# main.net
KiCad netlist of a schematic drawn in EAGLE
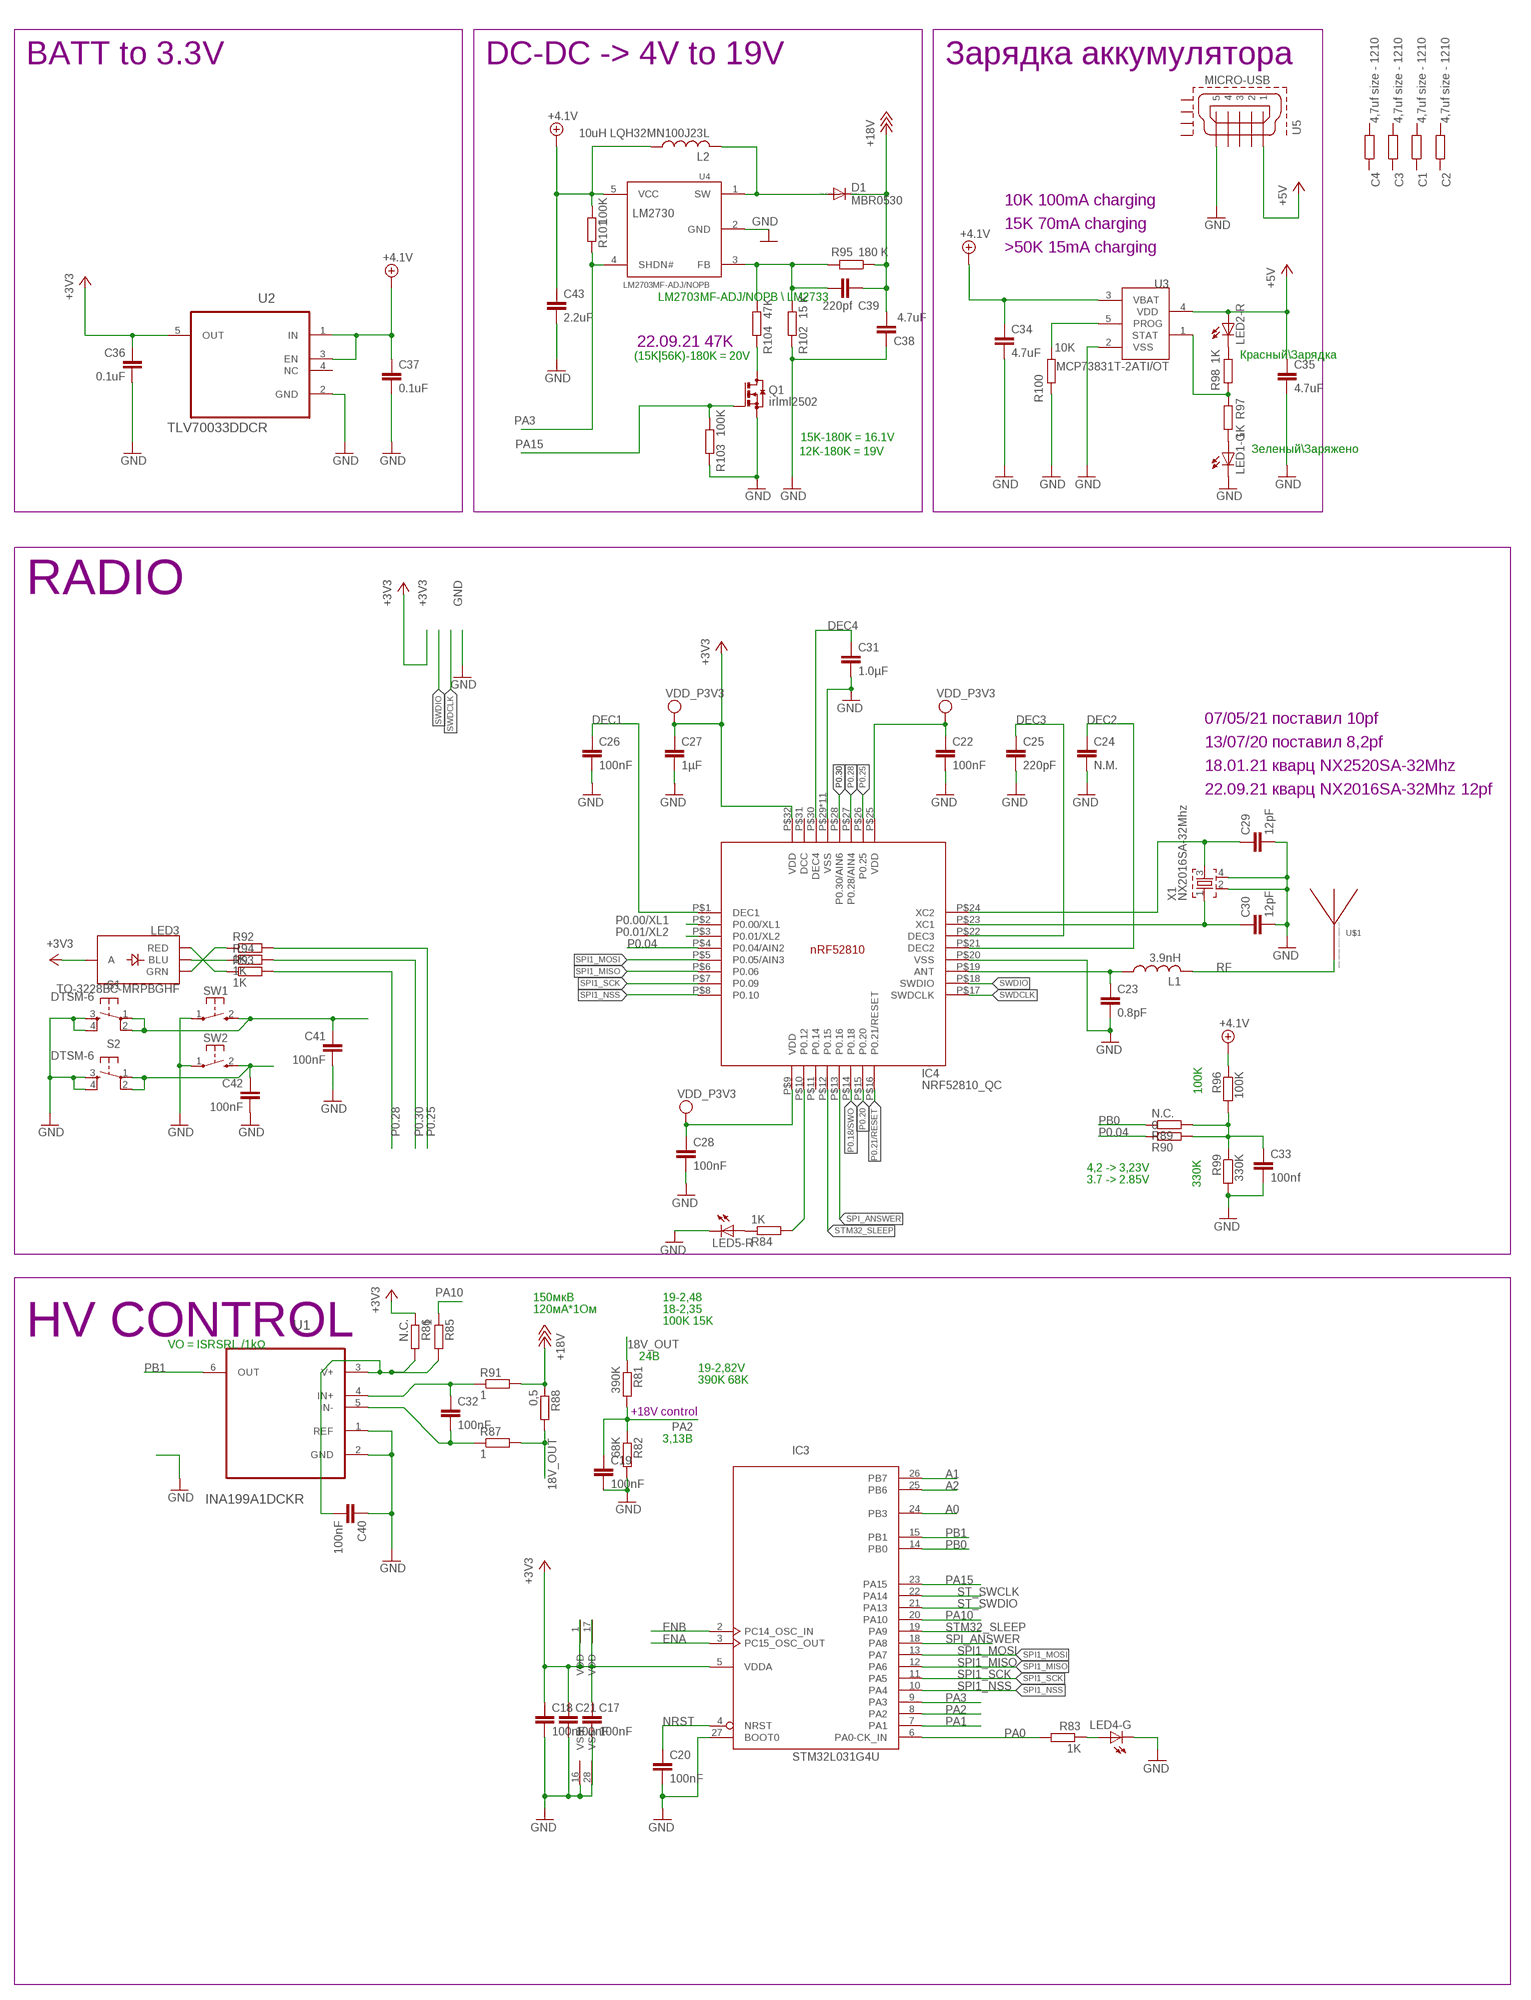
[diagram p0: schematic, sheet 1, part 1 of 2]
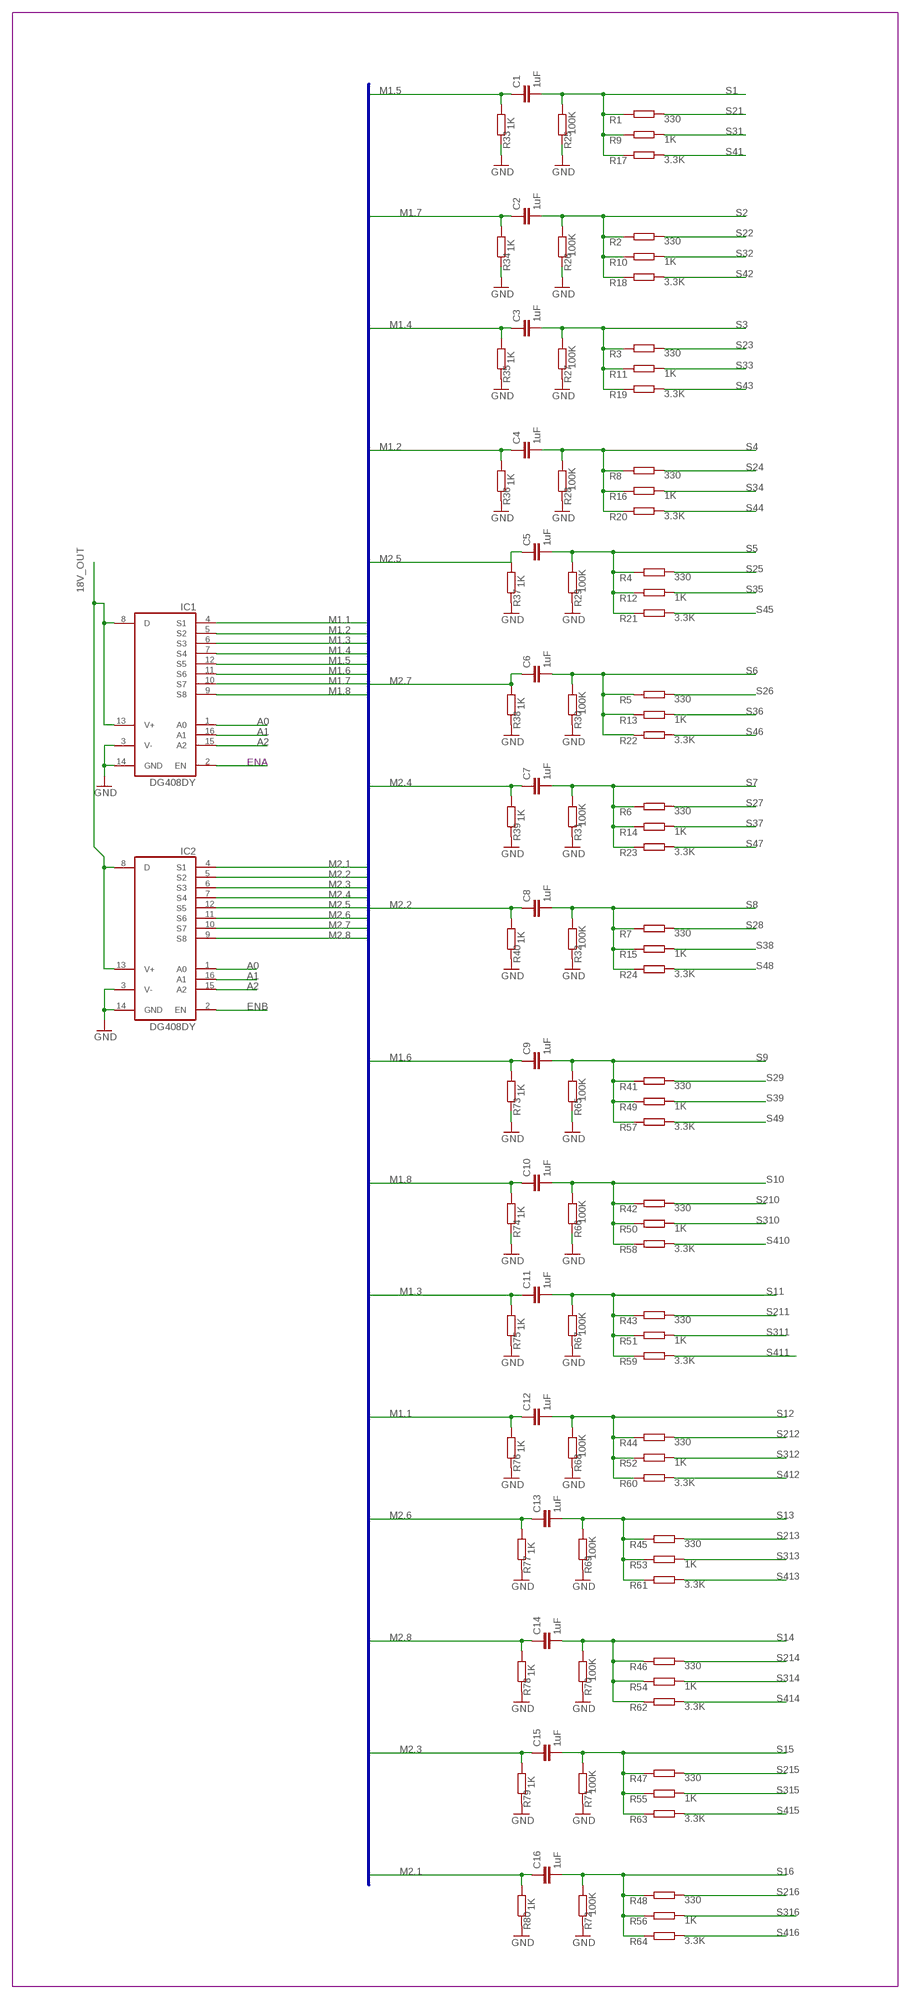
[diagram p1: schematic, sheet 1, part 2 of 2]

(export (version "E")
  (design (tool "Eeschema 10.0.6"))
  (components
    (comp (ref "C1")
      (value "1uF")
      (footprint "eagle-import:C0402")
      (libsource (lib "eagle-import") (part "C-EUC0402"))
    )
    (comp (ref "C2")
      (value "1uF")
      (footprint "eagle-import:C0402")
      (libsource (lib "eagle-import") (part "C-EUC0402"))
    )
    (comp (ref "C3")
      (value "1uF")
      (footprint "eagle-import:C0402")
      (libsource (lib "eagle-import") (part "C-EUC0402"))
    )
    (comp (ref "C4")
      (value "1uF")
      (footprint "eagle-import:C0402")
      (libsource (lib "eagle-import") (part "C-EUC0402"))
    )
    (comp (ref "C5")
      (value "1uF")
      (footprint "eagle-import:C0402")
      (libsource (lib "eagle-import") (part "C-EUC0402"))
    )
    (comp (ref "C6")
      (value "1uF")
      (footprint "eagle-import:C0402")
      (libsource (lib "eagle-import") (part "C-EUC0402"))
    )
    (comp (ref "C7")
      (value "1uF")
      (footprint "eagle-import:C0402")
      (libsource (lib "eagle-import") (part "C-EUC0402"))
    )
    (comp (ref "C8")
      (value "1uF")
      (footprint "eagle-import:C0402")
      (libsource (lib "eagle-import") (part "C-EUC0402"))
    )
    (comp (ref "C9")
      (value "1uF")
      (footprint "eagle-import:C0402")
      (libsource (lib "eagle-import") (part "C-EUC0402"))
    )
    (comp (ref "C10")
      (value "1uF")
      (footprint "eagle-import:C0402")
      (libsource (lib "eagle-import") (part "C-EUC0402"))
    )
    (comp (ref "C11")
      (value "1uF")
      (footprint "eagle-import:C0402")
      (libsource (lib "eagle-import") (part "C-EUC0402"))
    )
    (comp (ref "C12")
      (value "1uF")
      (footprint "eagle-import:C0402")
      (libsource (lib "eagle-import") (part "C-EUC0402"))
    )
    (comp (ref "C13")
      (value "1uF")
      (footprint "eagle-import:C0402")
      (libsource (lib "eagle-import") (part "C-EUC0402"))
    )
    (comp (ref "C14")
      (value "1uF")
      (footprint "eagle-import:C0402")
      (libsource (lib "eagle-import") (part "C-EUC0402"))
    )
    (comp (ref "C15")
      (value "1uF")
      (footprint "eagle-import:C0402")
      (libsource (lib "eagle-import") (part "C-EUC0402"))
    )
    (comp (ref "C16")
      (value "1uF")
      (footprint "eagle-import:C0402")
      (libsource (lib "eagle-import") (part "C-EUC0402"))
    )
    (comp (ref "C17")
      (value "100nF")
      (footprint "eagle-import:RESC0402_N")
      (libsource (lib "eagle-import") (part "CAPACITOR_0402_N"))
    )
    (comp (ref "C18")
      (value "100nF")
      (footprint "eagle-import:RESC0402_N")
      (libsource (lib "eagle-import") (part "CAPACITOR_0402_N"))
    )
    (comp (ref "C19")
      (value "100nF")
      (footprint "eagle-import:RESC0402_N")
      (libsource (lib "eagle-import") (part "CAPACITOR_0402_N"))
    )
    (comp (ref "C20")
      (value "100nF")
      (footprint "eagle-import:RESC0402_N")
      (libsource (lib "eagle-import") (part "CAPACITOR_0402_N"))
    )
    (comp (ref "C21")
      (value "100nF")
      (footprint "eagle-import:RESC0402_N")
      (libsource (lib "eagle-import") (part "CAPACITOR_0402_N"))
    )
    (comp (ref "C22")
      (value "100nF")
      (footprint "eagle-import:RESC0402_N")
      (libsource (lib "eagle-import") (part "CAPACITOR_0402_N"))
    )
    (comp (ref "C23")
      (value "0.8pF")
      (footprint "eagle-import:RESC0402_N")
      (libsource (lib "eagle-import") (part "CAPACITOR_0402_N"))
    )
    (comp (ref "C24")
      (value "N.M.")
      (footprint "eagle-import:RESC0402_N")
      (libsource (lib "eagle-import") (part "CAPACITOR_0402_N"))
    )
    (comp (ref "C25")
      (value "220pF")
      (footprint "eagle-import:RESC0402_N")
      (libsource (lib "eagle-import") (part "CAPACITOR_0402_N"))
    )
    (comp (ref "C26")
      (value "100nF")
      (footprint "eagle-import:RESC0402_N")
      (libsource (lib "eagle-import") (part "CAPACITOR_0402_N"))
    )
    (comp (ref "C27")
      (value "1µF")
      (footprint "eagle-import:RESC0603_N")
      (libsource (lib "eagle-import") (part "CAPACITOR_0603_N"))
    )
    (comp (ref "C28")
      (value "100nF")
      (footprint "eagle-import:RESC0402_N")
      (libsource (lib "eagle-import") (part "CAPACITOR_0402_N"))
    )
    (comp (ref "C29")
      (value "12pF")
      (footprint "eagle-import:RESC0402_N")
      (libsource (lib "eagle-import") (part "CAPACITOR_0402_N"))
    )
    (comp (ref "C30")
      (value "12pF")
      (footprint "eagle-import:RESC0402_N")
      (libsource (lib "eagle-import") (part "CAPACITOR_0402_N"))
    )
    (comp (ref "C31")
      (value "1.0µF")
      (footprint "eagle-import:RESC0402_M")
      (libsource (lib "eagle-import") (part "CAPACITOR_0402_M"))
    )
    (comp (ref "C32")
      (value "100nF")
      (footprint "eagle-import:RESC0402_N")
      (libsource (lib "eagle-import") (part "CAPACITOR_0402_N"))
    )
    (comp (ref "C33")
      (value "100nf")
      (footprint "eagle-import:RESC0402_N")
      (libsource (lib "eagle-import") (part "CAPACITOR_0402_N"))
    )
    (comp (ref "C34")
      (value "4.7uF")
      (footprint "eagle-import:C0805K")
      (libsource (lib "eagle-import") (part "C-EUC0805K"))
    )
    (comp (ref "C35")
      (value "4.7uF")
      (footprint "eagle-import:C0805K")
      (libsource (lib "eagle-import") (part "C-EUC0805K"))
    )
    (comp (ref "C36")
      (value "0.1uF")
      (footprint "eagle-import:C0402")
      (libsource (lib "eagle-import") (part "C-EUC0402"))
    )
    (comp (ref "C37")
      (value "0.1uF")
      (footprint "eagle-import:C0402")
      (libsource (lib "eagle-import") (part "C-EUC0402"))
    )
    (comp (ref "C38")
      (value "4.7uF")
      (footprint "eagle-import:C0805K")
      (libsource (lib "eagle-import") (part "C-EUC0805K"))
    )
    (comp (ref "C39")
      (value "220pf")
      (footprint "eagle-import:C0603K")
      (libsource (lib "eagle-import") (part "C-EUC0603K"))
    )
    (comp (ref "C40")
      (value "100nF")
      (footprint "eagle-import:RESC0402_N")
      (libsource (lib "eagle-import") (part "CAPACITOR_0402_N"))
    )
    (comp (ref "C41")
      (value "100nF")
      (footprint "eagle-import:RESC0402_N")
      (libsource (lib "eagle-import") (part "CAPACITOR_0402_N"))
    )
    (comp (ref "C42")
      (value "100nF")
      (footprint "eagle-import:RESC0402_N")
      (libsource (lib "eagle-import") (part "CAPACITOR_0402_N"))
    )
    (comp (ref "C43")
      (value "2.2uF")
      (footprint "eagle-import:C0805K")
      (libsource (lib "eagle-import") (part "C-EUC0805K"))
    )
    (comp (ref "D1")
      (value "MBR0530")
      (footprint "eagle-import:SOD123")
      (libsource (lib "eagle-import") (part "MBR0520LT"))
    )
    (comp (ref "IC1")
      (value "DG408DY")
      (footprint "eagle-import:SO16")
      (libsource (lib "eagle-import") (part "DG408DY"))
    )
    (comp (ref "IC2")
      (value "DG408DY")
      (footprint "eagle-import:SO16")
      (libsource (lib "eagle-import") (part "DG408DY"))
    )
    (comp (ref "IC3")
      (value "STM32L031G4U")
      (footprint "eagle-import:UFQFPN28")
      (libsource (lib "eagle-import") (part "STM32L031GU4"))
    )
    (comp (ref "IC4")
      (value "NRF52810_QC")
      (footprint "eagle-import:QFN50P500X500X90-32_N")
      (libsource (lib "eagle-import") (part "NRF52810_QC"))
    )
    (comp (ref "L1")
      (value "3.9nH")
      (footprint "eagle-import:RESC0402_N")
      (libsource (lib "eagle-import") (part "INDUCTOR_0402_N"))
    )
    (comp (ref "L2")
      (value "10uH LQH32MN100J23L")
      (footprint "eagle-import:L2825P")
      (libsource (lib "eagle-import") (part "L-USL2825P"))
    )
    (comp (ref "LED1-G")
      (value "LEDCHIP-LED0603")
      (footprint "eagle-import:CHIP-LED0603")
      (libsource (lib "eagle-import") (part "LEDCHIP-LED0603"))
    )
    (comp (ref "LED2-R")
      (value "LEDCHIP-LED0603")
      (footprint "eagle-import:CHIP-LED0603")
      (libsource (lib "eagle-import") (part "LEDCHIP-LED0603"))
    )
    (comp (ref "LED3")
      (value "TO-3228BC-MRPBGHF")
      (footprint "eagle-import:LED-TRICOLOR-SMD")
      (libsource (lib "eagle-import") (part "LED-RGB-CASMD"))
    )
    (comp (ref "LED4-G")
      (value "LEDCHIPLED_0603")
      (footprint "eagle-import:CHIPLED_0603")
      (libsource (lib "eagle-import") (part "LEDCHIPLED_0603"))
    )
    (comp (ref "LED5-R")
      (value "LEDCHIPLED_0603")
      (footprint "eagle-import:CHIPLED_0603")
      (libsource (lib "eagle-import") (part "LEDCHIPLED_0603"))
    )
    (comp (ref "Q1")
      (value "irlml2502")
      (footprint "eagle-import:SOT23")
      (libsource (lib "eagle-import") (part "IRLML_N_TYPE"))
    )
    (comp (ref "R1")
      (value "330")
      (footprint "eagle-import:R0402")
      (libsource (lib "eagle-import") (part "R-EU_R0402"))
    )
    (comp (ref "R2")
      (value "330")
      (footprint "eagle-import:R0402")
      (libsource (lib "eagle-import") (part "R-EU_R0402"))
    )
    (comp (ref "R3")
      (value "330")
      (footprint "eagle-import:R0402")
      (libsource (lib "eagle-import") (part "R-EU_R0402"))
    )
    (comp (ref "R4")
      (value "330")
      (footprint "eagle-import:R0402")
      (libsource (lib "eagle-import") (part "R-EU_R0402"))
    )
    (comp (ref "R5")
      (value "330")
      (footprint "eagle-import:R0402")
      (libsource (lib "eagle-import") (part "R-EU_R0402"))
    )
    (comp (ref "R6")
      (value "330")
      (footprint "eagle-import:R0402")
      (libsource (lib "eagle-import") (part "R-EU_R0402"))
    )
    (comp (ref "R7")
      (value "330")
      (footprint "eagle-import:R0402")
      (libsource (lib "eagle-import") (part "R-EU_R0402"))
    )
    (comp (ref "R8")
      (value "330")
      (footprint "eagle-import:R0402")
      (libsource (lib "eagle-import") (part "R-EU_R0402"))
    )
    (comp (ref "R9")
      (value "1K")
      (footprint "eagle-import:R0402")
      (libsource (lib "eagle-import") (part "R-EU_R0402"))
    )
    (comp (ref "R10")
      (value "1K")
      (footprint "eagle-import:R0402")
      (libsource (lib "eagle-import") (part "R-EU_R0402"))
    )
    (comp (ref "R11")
      (value "1K")
      (footprint "eagle-import:R0402")
      (libsource (lib "eagle-import") (part "R-EU_R0402"))
    )
    (comp (ref "R12")
      (value "1K")
      (footprint "eagle-import:R0402")
      (libsource (lib "eagle-import") (part "R-EU_R0402"))
    )
    (comp (ref "R13")
      (value "1K")
      (footprint "eagle-import:R0402")
      (libsource (lib "eagle-import") (part "R-EU_R0402"))
    )
    (comp (ref "R14")
      (value "1K")
      (footprint "eagle-import:R0402")
      (libsource (lib "eagle-import") (part "R-EU_R0402"))
    )
    (comp (ref "R15")
      (value "1K")
      (footprint "eagle-import:R0402")
      (libsource (lib "eagle-import") (part "R-EU_R0402"))
    )
    (comp (ref "R16")
      (value "1K")
      (footprint "eagle-import:R0402")
      (libsource (lib "eagle-import") (part "R-EU_R0402"))
    )
    (comp (ref "R17")
      (value "3.3K")
      (footprint "eagle-import:R0402")
      (libsource (lib "eagle-import") (part "R-EU_R0402"))
    )
    (comp (ref "R18")
      (value "3.3K")
      (footprint "eagle-import:R0402")
      (libsource (lib "eagle-import") (part "R-EU_R0402"))
    )
    (comp (ref "R19")
      (value "3.3K")
      (footprint "eagle-import:R0402")
      (libsource (lib "eagle-import") (part "R-EU_R0402"))
    )
    (comp (ref "R20")
      (value "3.3K")
      (footprint "eagle-import:R0402")
      (libsource (lib "eagle-import") (part "R-EU_R0402"))
    )
    (comp (ref "R21")
      (value "3.3K")
      (footprint "eagle-import:R0402")
      (libsource (lib "eagle-import") (part "R-EU_R0402"))
    )
    (comp (ref "R22")
      (value "3.3K")
      (footprint "eagle-import:R0402")
      (libsource (lib "eagle-import") (part "R-EU_R0402"))
    )
    (comp (ref "R23")
      (value "3.3K")
      (footprint "eagle-import:R0402")
      (libsource (lib "eagle-import") (part "R-EU_R0402"))
    )
    (comp (ref "R24")
      (value "3.3K")
      (footprint "eagle-import:R0402")
      (libsource (lib "eagle-import") (part "R-EU_R0402"))
    )
    (comp (ref "R25")
      (value "100K")
      (footprint "eagle-import:R0402")
      (libsource (lib "eagle-import") (part "R-EU_R0402"))
    )
    (comp (ref "R26")
      (value "100K")
      (footprint "eagle-import:R0402")
      (libsource (lib "eagle-import") (part "R-EU_R0402"))
    )
    (comp (ref "R27")
      (value "100K")
      (footprint "eagle-import:R0402")
      (libsource (lib "eagle-import") (part "R-EU_R0402"))
    )
    (comp (ref "R28")
      (value "100K")
      (footprint "eagle-import:R0402")
      (libsource (lib "eagle-import") (part "R-EU_R0402"))
    )
    (comp (ref "R29")
      (value "100K")
      (footprint "eagle-import:R0402")
      (libsource (lib "eagle-import") (part "R-EU_R0402"))
    )
    (comp (ref "R30")
      (value "100K")
      (footprint "eagle-import:R0402")
      (libsource (lib "eagle-import") (part "R-EU_R0402"))
    )
    (comp (ref "R31")
      (value "100K")
      (footprint "eagle-import:R0402")
      (libsource (lib "eagle-import") (part "R-EU_R0402"))
    )
    (comp (ref "R32")
      (value "100K")
      (footprint "eagle-import:R0402")
      (libsource (lib "eagle-import") (part "R-EU_R0402"))
    )
    (comp (ref "R33")
      (value "1K")
      (footprint "eagle-import:R0402")
      (libsource (lib "eagle-import") (part "R-EU_R0402"))
    )
    (comp (ref "R34")
      (value "1K")
      (footprint "eagle-import:R0402")
      (libsource (lib "eagle-import") (part "R-EU_R0402"))
    )
    (comp (ref "R35")
      (value "1K")
      (footprint "eagle-import:R0402")
      (libsource (lib "eagle-import") (part "R-EU_R0402"))
    )
    (comp (ref "R36")
      (value "1K")
      (footprint "eagle-import:R0402")
      (libsource (lib "eagle-import") (part "R-EU_R0402"))
    )
    (comp (ref "R37")
      (value "1K")
      (footprint "eagle-import:R0402")
      (libsource (lib "eagle-import") (part "R-EU_R0402"))
    )
    (comp (ref "R38")
      (value "1K")
      (footprint "eagle-import:R0402")
      (libsource (lib "eagle-import") (part "R-EU_R0402"))
    )
    (comp (ref "R39")
      (value "1K")
      (footprint "eagle-import:R0402")
      (libsource (lib "eagle-import") (part "R-EU_R0402"))
    )
    (comp (ref "R40")
      (value "1K")
      (footprint "eagle-import:R0402")
      (libsource (lib "eagle-import") (part "R-EU_R0402"))
    )
    (comp (ref "R41")
      (value "330")
      (footprint "eagle-import:R0402")
      (libsource (lib "eagle-import") (part "R-EU_R0402"))
    )
    (comp (ref "R42")
      (value "330")
      (footprint "eagle-import:R0402")
      (libsource (lib "eagle-import") (part "R-EU_R0402"))
    )
    (comp (ref "R43")
      (value "330")
      (footprint "eagle-import:R0402")
      (libsource (lib "eagle-import") (part "R-EU_R0402"))
    )
    (comp (ref "R44")
      (value "330")
      (footprint "eagle-import:R0402")
      (libsource (lib "eagle-import") (part "R-EU_R0402"))
    )
    (comp (ref "R45")
      (value "330")
      (footprint "eagle-import:R0402")
      (libsource (lib "eagle-import") (part "R-EU_R0402"))
    )
    (comp (ref "R46")
      (value "330")
      (footprint "eagle-import:R0402")
      (libsource (lib "eagle-import") (part "R-EU_R0402"))
    )
    (comp (ref "R47")
      (value "330")
      (footprint "eagle-import:R0402")
      (libsource (lib "eagle-import") (part "R-EU_R0402"))
    )
    (comp (ref "R48")
      (value "330")
      (footprint "eagle-import:R0402")
      (libsource (lib "eagle-import") (part "R-EU_R0402"))
    )
    (comp (ref "R49")
      (value "1K")
      (footprint "eagle-import:R0402")
      (libsource (lib "eagle-import") (part "R-EU_R0402"))
    )
    (comp (ref "R50")
      (value "1K")
      (footprint "eagle-import:R0402")
      (libsource (lib "eagle-import") (part "R-EU_R0402"))
    )
    (comp (ref "R51")
      (value "1K")
      (footprint "eagle-import:R0402")
      (libsource (lib "eagle-import") (part "R-EU_R0402"))
    )
    (comp (ref "R52")
      (value "1K")
      (footprint "eagle-import:R0402")
      (libsource (lib "eagle-import") (part "R-EU_R0402"))
    )
    (comp (ref "R53")
      (value "1K")
      (footprint "eagle-import:R0402")
      (libsource (lib "eagle-import") (part "R-EU_R0402"))
    )
    (comp (ref "R54")
      (value "1K")
      (footprint "eagle-import:R0402")
      (libsource (lib "eagle-import") (part "R-EU_R0402"))
    )
    (comp (ref "R55")
      (value "1K")
      (footprint "eagle-import:R0402")
      (libsource (lib "eagle-import") (part "R-EU_R0402"))
    )
    (comp (ref "R56")
      (value "1K")
      (footprint "eagle-import:R0402")
      (libsource (lib "eagle-import") (part "R-EU_R0402"))
    )
    (comp (ref "R57")
      (value "3.3K")
      (footprint "eagle-import:R0402")
      (libsource (lib "eagle-import") (part "R-EU_R0402"))
    )
    (comp (ref "R58")
      (value "3.3K")
      (footprint "eagle-import:R0402")
      (libsource (lib "eagle-import") (part "R-EU_R0402"))
    )
    (comp (ref "R59")
      (value "3.3K")
      (footprint "eagle-import:R0402")
      (libsource (lib "eagle-import") (part "R-EU_R0402"))
    )
    (comp (ref "R60")
      (value "3.3K")
      (footprint "eagle-import:R0402")
      (libsource (lib "eagle-import") (part "R-EU_R0402"))
    )
    (comp (ref "R61")
      (value "3.3K")
      (footprint "eagle-import:R0402")
      (libsource (lib "eagle-import") (part "R-EU_R0402"))
    )
    (comp (ref "R62")
      (value "3.3K")
      (footprint "eagle-import:R0402")
      (libsource (lib "eagle-import") (part "R-EU_R0402"))
    )
    (comp (ref "R63")
      (value "3.3K")
      (footprint "eagle-import:R0402")
      (libsource (lib "eagle-import") (part "R-EU_R0402"))
    )
    (comp (ref "R64")
      (value "3.3K")
      (footprint "eagle-import:R0402")
      (libsource (lib "eagle-import") (part "R-EU_R0402"))
    )
    (comp (ref "R65")
      (value "100K")
      (footprint "eagle-import:R0402")
      (libsource (lib "eagle-import") (part "R-EU_R0402"))
    )
    (comp (ref "R66")
      (value "100K")
      (footprint "eagle-import:R0402")
      (libsource (lib "eagle-import") (part "R-EU_R0402"))
    )
    (comp (ref "R67")
      (value "100K")
      (footprint "eagle-import:R0402")
      (libsource (lib "eagle-import") (part "R-EU_R0402"))
    )
    (comp (ref "R68")
      (value "100K")
      (footprint "eagle-import:R0402")
      (libsource (lib "eagle-import") (part "R-EU_R0402"))
    )
    (comp (ref "R69")
      (value "100K")
      (footprint "eagle-import:R0402")
      (libsource (lib "eagle-import") (part "R-EU_R0402"))
    )
    (comp (ref "R70")
      (value "100K")
      (footprint "eagle-import:R0402")
      (libsource (lib "eagle-import") (part "R-EU_R0402"))
    )
    (comp (ref "R71")
      (value "100K")
      (footprint "eagle-import:R0402")
      (libsource (lib "eagle-import") (part "R-EU_R0402"))
    )
    (comp (ref "R72")
      (value "100K")
      (footprint "eagle-import:R0402")
      (libsource (lib "eagle-import") (part "R-EU_R0402"))
    )
    (comp (ref "R73")
      (value "1K")
      (footprint "eagle-import:R0402")
      (libsource (lib "eagle-import") (part "R-EU_R0402"))
    )
    (comp (ref "R74")
      (value "1K")
      (footprint "eagle-import:R0402")
      (libsource (lib "eagle-import") (part "R-EU_R0402"))
    )
    (comp (ref "R75")
      (value "1K")
      (footprint "eagle-import:R0402")
      (libsource (lib "eagle-import") (part "R-EU_R0402"))
    )
    (comp (ref "R76")
      (value "1K")
      (footprint "eagle-import:R0402")
      (libsource (lib "eagle-import") (part "R-EU_R0402"))
    )
    (comp (ref "R77")
      (value "1K")
      (footprint "eagle-import:R0402")
      (libsource (lib "eagle-import") (part "R-EU_R0402"))
    )
    (comp (ref "R78")
      (value "1K")
      (footprint "eagle-import:R0402")
      (libsource (lib "eagle-import") (part "R-EU_R0402"))
    )
    (comp (ref "R79")
      (value "1K")
      (footprint "eagle-import:R0402")
      (libsource (lib "eagle-import") (part "R-EU_R0402"))
    )
    (comp (ref "R80")
      (value "1K")
      (footprint "eagle-import:R0402")
      (libsource (lib "eagle-import") (part "R-EU_R0402"))
    )
    (comp (ref "R81")
      (value "390K")
      (footprint "eagle-import:R0402")
      (libsource (lib "eagle-import") (part "R-EU_R0402"))
    )
    (comp (ref "R82")
      (value "68K")
      (footprint "eagle-import:R0402")
      (libsource (lib "eagle-import") (part "R-EU_R0402"))
    )
    (comp (ref "R83")
      (value "1K")
      (footprint "eagle-import:R0603")
      (libsource (lib "eagle-import") (part "R-EU_R0603"))
    )
    (comp (ref "R84")
      (value "1K")
      (footprint "eagle-import:R0603")
      (libsource (lib "eagle-import") (part "R-EU_R0603"))
    )
    (comp (ref "R85")
      (value "1")
      (footprint "eagle-import:R0402")
      (libsource (lib "eagle-import") (part "R-EU_R0402"))
    )
    (comp (ref "R86")
      (value "N.C.")
      (footprint "eagle-import:R0402")
      (libsource (lib "eagle-import") (part "R-EU_R0402"))
    )
    (comp (ref "R87")
      (value "1")
      (footprint "eagle-import:R0402")
      (libsource (lib "eagle-import") (part "R-EU_R0402"))
    )
    (comp (ref "R88")
      (value "0,5")
      (footprint "eagle-import:R0603")
      (libsource (lib "eagle-import") (part "R-EU_R0603"))
    )
    (comp (ref "R89")
      (value "N.C.")
      (footprint "eagle-import:R0402")
      (libsource (lib "eagle-import") (part "R-EU_R0402"))
    )
    (comp (ref "R90")
      (value "0")
      (footprint "eagle-import:R0402")
      (libsource (lib "eagle-import") (part "R-EU_R0402"))
    )
    (comp (ref "R91")
      (value "1")
      (footprint "eagle-import:R0402")
      (libsource (lib "eagle-import") (part "R-EU_R0402"))
    )
    (comp (ref "R92")
      (value "1K")
      (footprint "eagle-import:R0402")
      (libsource (lib "eagle-import") (part "R-EU_R0402"))
    )
    (comp (ref "R93")
      (value "1K")
      (footprint "eagle-import:R0402")
      (libsource (lib "eagle-import") (part "R-EU_R0402"))
    )
    (comp (ref "R94")
      (value "1K")
      (footprint "eagle-import:R0402")
      (libsource (lib "eagle-import") (part "R-EU_R0402"))
    )
    (comp (ref "R95")
      (value "180 K")
      (footprint "eagle-import:R0603")
      (libsource (lib "eagle-import") (part "R-EU_R0603"))
    )
    (comp (ref "R96")
      (value "100K")
      (footprint "eagle-import:R0402")
      (libsource (lib "eagle-import") (part "R-EU_R0402"))
    )
    (comp (ref "R97")
      (value "1K")
      (footprint "eagle-import:R0603")
      (libsource (lib "eagle-import") (part "R-EU_R0603"))
    )
    (comp (ref "R98")
      (value "1K")
      (footprint "eagle-import:R0603")
      (libsource (lib "eagle-import") (part "R-EU_R0603"))
    )
    (comp (ref "R99")
      (value "330K")
      (footprint "eagle-import:R0402")
      (libsource (lib "eagle-import") (part "R-EU_R0402"))
    )
    (comp (ref "R100")
      (value "10K")
      (footprint "eagle-import:R0402")
      (libsource (lib "eagle-import") (part "R-EU_R0402"))
    )
    (comp (ref "R101")
      (value "100K")
      (footprint "eagle-import:R0402")
      (libsource (lib "eagle-import") (part "R-EU_R0402"))
    )
    (comp (ref "R102")
      (value "15 K")
      (footprint "eagle-import:R0603")
      (libsource (lib "eagle-import") (part "R-EU_R0603"))
    )
    (comp (ref "R103")
      (value "100K")
      (footprint "eagle-import:R0603")
      (libsource (lib "eagle-import") (part "R-EU_R0603"))
    )
    (comp (ref "R104")
      (value "47K")
      (footprint "eagle-import:R0603")
      (libsource (lib "eagle-import") (part "R-EU_R0603"))
    )
    (comp (ref "S1")
      (value "DTSM-6")
      (footprint "eagle-import:DTSM-6")
      (libsource (lib "eagle-import") (part "DTSM-6"))
    )
    (comp (ref "S2")
      (value "DTSM-6")
      (footprint "eagle-import:DTSM-6")
      (libsource (lib "eagle-import") (part "DTSM-6"))
    )
    (comp (ref "SW1")
      (value "KSS-2EG4430")
      (footprint "eagle-import:KSS-2EG4430")
      (libsource (lib "eagle-import") (part "KSS-2EG4430"))
    )
    (comp (ref "SW2")
      (value "KSS-2EG4430")
      (footprint "eagle-import:KSS-2EG4430")
      (libsource (lib "eagle-import") (part "KSS-2EG4430"))
    )
    (comp (ref "U$1")
      (value "ANTENNA_QUARTER-WAVE_MONOPOLE_MEANDERED_LEFT")
      (footprint "eagle-import:QWMP_MEANDERED_LEFT_+6")
      (libsource (lib "eagle-import") (part "ANTENNA_QUARTER-WAVE_MONOPOLE_MEANDERED_LEFT"))
    )
    (comp (ref "U1")
      (value "INA199A1DCKR")
      (footprint "eagle-import:SOT65P210X110-6N")
      (libsource (lib "eagle-import") (part "INA199A1DCKR"))
    )
    (comp (ref "U2")
      (value "TLV70033DDCR")
      (footprint "eagle-import:SOT95P280X110-5N")
      (libsource (lib "eagle-import") (part "TLV70033DDCR"))
    )
    (comp (ref "U3")
      (value "MCP73831T-2ATI/OT")
      (footprint "eagle-import:SOT23-5L")
      (libsource (lib "eagle-import") (part "MCP73831"))
    )
    (comp (ref "U4")
      (value "LM2703MF-ADJ/NOPB")
      (footprint "eagle-import:SOT23-5")
      (libsource (lib "eagle-import") (part "LM2703"))
    )
    (comp (ref "U5")
      (value "MICRO-USB")
      (footprint "eagle-import:47589-0001")
      (libsource (lib "eagle-import") (part "MICRO-USB-RECEPTACLE47589-0001"))
    )
    (comp (ref "X1")
      (value "NX2016SA-32Mhz")
      (footprint "eagle-import:BT-XTAL_2016_N")
      (libsource (lib "eagle-import") (part "XTAL_32MHZ"))
    )
    (comp (ref "С1")
      (value "4,7uf size - 1210")
      (footprint "eagle-import:R1206")
      (libsource (lib "eagle-import") (part "R-EU_R1206"))
    )
    (comp (ref "С2")
      (value "4,7uf size - 1210")
      (footprint "eagle-import:R1206")
      (libsource (lib "eagle-import") (part "R-EU_R1206"))
    )
    (comp (ref "С3")
      (value "4,7uf size - 1210")
      (footprint "eagle-import:R1206")
      (libsource (lib "eagle-import") (part "R-EU_R1206"))
    )
    (comp (ref "С4")
      (value "4,7uf size - 1210")
      (footprint "eagle-import:R1206")
      (libsource (lib "eagle-import") (part "R-EU_R1206"))
    )
  )
  (nets
    (net (code "1") (name "+3V3") (class "Default")
      (node (ref "C17") (pin "1") (pinfunction "1_1") (pintype "passive"))
      (node (ref "C18") (pin "1") (pinfunction "1_1") (pintype "passive"))
      (node (ref "C21") (pin "1") (pinfunction "1_1") (pintype "passive"))
      (node (ref "C22") (pin "1") (pinfunction "1_1") (pintype "passive"))
      (node (ref "C27") (pin "1") (pinfunction "1_1") (pintype "passive"))
      (node (ref "C28") (pin "1") (pinfunction "1_1") (pintype "passive"))
      (node (ref "C36") (pin "1") (pinfunction "1_1") (pintype "passive"))
      (node (ref "IC3") (pin "1") (pinfunction "VDD_1") (pintype "power_in"))
      (node (ref "IC3") (pin "17") (pinfunction "VDD_17") (pintype "power_in"))
      (node (ref "IC3") (pin "5") (pinfunction "VDDA_5") (pintype "power_in"))
      (node (ref "IC4") (pin "P$25") (pinfunction "VDD_P$25") (pintype "bidirectional"))
      (node (ref "IC4") (pin "P$32") (pinfunction "VDD_P$32") (pintype "bidirectional"))
      (node (ref "IC4") (pin "P$9") (pinfunction "VDD_P$9") (pintype "bidirectional"))
      (node (ref "LED3") (pin "A") (pinfunction "A_A") (pintype "bidirectional"))
      (node (ref "R86") (pin "1") (pinfunction "1_1") (pintype "passive"))
      (node (ref "U2") (pin "5") (pinfunction "OUT_5") (pintype "output"))
    )
    (net (code "2") (name "+4.1V") (class "Default")
      (node (ref "C34") (pin "1") (pinfunction "1_1") (pintype "passive"))
      (node (ref "C37") (pin "1") (pinfunction "1_1") (pintype "passive"))
      (node (ref "C43") (pin "1") (pinfunction "1_1") (pintype "passive"))
      (node (ref "L2") (pin "1") (pinfunction "1_1") (pintype "passive"))
      (node (ref "R101") (pin "1") (pinfunction "1_1") (pintype "passive"))
      (node (ref "R96") (pin "1") (pinfunction "1_1") (pintype "passive"))
      (node (ref "U2") (pin "1") (pinfunction "IN_1") (pintype "power_in"))
      (node (ref "U2") (pin "3") (pinfunction "EN_3") (pintype "input"))
      (node (ref "U3") (pin "3") (pinfunction "VBAT_3") (pintype "bidirectional"))
      (node (ref "U4") (pin "5") (pinfunction "VCC_5") (pintype "power_in"))
    )
    (net (code "3") (name "+5V") (class "Default")
      (node (ref "C35") (pin "1") (pinfunction "1_1") (pintype "passive"))
      (node (ref "LED2-R") (pin "A") (pinfunction "A_A") (pintype "passive"))
      (node (ref "U3") (pin "4") (pinfunction "VDD_4") (pintype "bidirectional"))
      (node (ref "U5") (pin "1") (pinfunction "1_1") (pintype "input"))
    )
    (net (code "4") (name "+18V") (class "Default")
      (node (ref "C38") (pin "2") (pinfunction "2_2") (pintype "passive"))
      (node (ref "C39") (pin "1") (pinfunction "1_1") (pintype "passive"))
      (node (ref "D1") (pin "C") (pinfunction "C_C") (pintype "passive"))
      (node (ref "R88") (pin "1") (pinfunction "1_1") (pintype "passive"))
      (node (ref "R91") (pin "2") (pinfunction "2_2") (pintype "passive"))
      (node (ref "R95") (pin "1") (pinfunction "1_1") (pintype "passive"))
    )
    (net (code "5") (name "/18V_OUT") (class "Default")
      (node (ref "IC1") (pin "13") (pinfunction "V+_13") (pintype "power_in"))
      (node (ref "IC1") (pin "8") (pinfunction "D_8") (pintype "passive"))
      (node (ref "IC2") (pin "13") (pinfunction "V+_13") (pintype "power_in"))
      (node (ref "IC2") (pin "8") (pinfunction "D_8") (pintype "passive"))
      (node (ref "R81") (pin "1") (pinfunction "1_1") (pintype "passive"))
      (node (ref "R87") (pin "2") (pinfunction "2_2") (pintype "passive"))
      (node (ref "R88") (pin "2") (pinfunction "2_2") (pintype "passive"))
    )
    (net (code "6") (name "/A0") (class "Default")
      (node (ref "IC1") (pin "1") (pinfunction "A0_1") (pintype "input"))
      (node (ref "IC2") (pin "1") (pinfunction "A0_1") (pintype "input"))
      (node (ref "IC3") (pin "24") (pinfunction "PB3_24") (pintype "bidirectional"))
    )
    (net (code "7") (name "/A1") (class "Default")
      (node (ref "IC1") (pin "16") (pinfunction "A1_16") (pintype "input"))
      (node (ref "IC2") (pin "16") (pinfunction "A1_16") (pintype "input"))
      (node (ref "IC3") (pin "26") (pinfunction "PB7_26") (pintype "bidirectional"))
    )
    (net (code "8") (name "/A2") (class "Default")
      (node (ref "IC1") (pin "15") (pinfunction "A2_15") (pintype "input"))
      (node (ref "IC2") (pin "15") (pinfunction "A2_15") (pintype "input"))
      (node (ref "IC3") (pin "25") (pinfunction "PB6_25") (pintype "bidirectional"))
    )
    (net (code "9") (name "/DEC1") (class "Default")
      (node (ref "C26") (pin "1") (pinfunction "1_1") (pintype "passive"))
      (node (ref "IC4") (pin "P$1") (pinfunction "DEC1_P$1") (pintype "bidirectional"))
    )
    (net (code "10") (name "/DEC2") (class "Default")
      (node (ref "C24") (pin "1") (pinfunction "1_1") (pintype "passive"))
      (node (ref "IC4") (pin "P$21") (pinfunction "DEC2_P$21") (pintype "bidirectional"))
    )
    (net (code "11") (name "/DEC3") (class "Default")
      (node (ref "C25") (pin "1") (pinfunction "1_1") (pintype "passive"))
      (node (ref "IC4") (pin "P$22") (pinfunction "DEC3_P$22") (pintype "bidirectional"))
    )
    (net (code "12") (name "/DEC4") (class "Default")
      (node (ref "C31") (pin "1") (pinfunction "1_1") (pintype "passive"))
      (node (ref "IC4") (pin "P$30") (pinfunction "DEC4_P$30") (pintype "bidirectional"))
    )
    (net (code "13") (name "/ENA") (class "Default")
      (node (ref "IC1") (pin "2") (pinfunction "EN_2") (pintype "input"))
      (node (ref "IC3") (pin "3") (pinfunction "PC15_OSC_OUT_3") (pintype "bidirectional"))
    )
    (net (code "14") (name "/ENB") (class "Default")
      (node (ref "IC2") (pin "2") (pinfunction "EN_2") (pintype "input"))
      (node (ref "IC3") (pin "2") (pinfunction "PC14_OSC_IN_2") (pintype "bidirectional"))
    )
    (net (code "15") (name "/M1.1") (class "Default")
      (node (ref "C12") (pin "1") (pinfunction "1_1") (pintype "passive"))
      (node (ref "IC1") (pin "4") (pinfunction "S1_4") (pintype "passive"))
      (node (ref "R76") (pin "2") (pinfunction "2_2") (pintype "passive"))
    )
    (net (code "16") (name "/M1.2") (class "Default")
      (node (ref "C4") (pin "1") (pinfunction "1_1") (pintype "passive"))
      (node (ref "IC1") (pin "5") (pinfunction "S2_5") (pintype "passive"))
      (node (ref "R36") (pin "2") (pinfunction "2_2") (pintype "passive"))
    )
    (net (code "17") (name "/M1.3") (class "Default")
      (node (ref "C11") (pin "1") (pinfunction "1_1") (pintype "passive"))
      (node (ref "IC1") (pin "6") (pinfunction "S3_6") (pintype "passive"))
      (node (ref "R75") (pin "2") (pinfunction "2_2") (pintype "passive"))
    )
    (net (code "18") (name "/M1.4") (class "Default")
      (node (ref "C3") (pin "1") (pinfunction "1_1") (pintype "passive"))
      (node (ref "IC1") (pin "7") (pinfunction "S4_7") (pintype "passive"))
      (node (ref "R35") (pin "2") (pinfunction "2_2") (pintype "passive"))
    )
    (net (code "19") (name "/M1.5") (class "Default")
      (node (ref "C1") (pin "1") (pinfunction "1_1") (pintype "passive"))
      (node (ref "IC1") (pin "12") (pinfunction "S5_12") (pintype "passive"))
      (node (ref "R33") (pin "2") (pinfunction "2_2") (pintype "passive"))
    )
    (net (code "20") (name "/M1.6") (class "Default")
      (node (ref "C9") (pin "1") (pinfunction "1_1") (pintype "passive"))
      (node (ref "IC1") (pin "11") (pinfunction "S6_11") (pintype "passive"))
      (node (ref "R73") (pin "2") (pinfunction "2_2") (pintype "passive"))
    )
    (net (code "21") (name "/M1.7") (class "Default")
      (node (ref "C2") (pin "1") (pinfunction "1_1") (pintype "passive"))
      (node (ref "IC1") (pin "10") (pinfunction "S7_10") (pintype "passive"))
      (node (ref "R34") (pin "2") (pinfunction "2_2") (pintype "passive"))
    )
    (net (code "22") (name "/M1.8") (class "Default")
      (node (ref "C10") (pin "1") (pinfunction "1_1") (pintype "passive"))
      (node (ref "IC1") (pin "9") (pinfunction "S8_9") (pintype "passive"))
      (node (ref "R74") (pin "2") (pinfunction "2_2") (pintype "passive"))
    )
    (net (code "23") (name "/M2.1") (class "Default")
      (node (ref "C16") (pin "1") (pinfunction "1_1") (pintype "passive"))
      (node (ref "IC2") (pin "4") (pinfunction "S1_4") (pintype "passive"))
      (node (ref "R80") (pin "2") (pinfunction "2_2") (pintype "passive"))
    )
    (net (code "24") (name "/M2.2") (class "Default")
      (node (ref "C8") (pin "1") (pinfunction "1_1") (pintype "passive"))
      (node (ref "IC2") (pin "5") (pinfunction "S2_5") (pintype "passive"))
      (node (ref "R40") (pin "2") (pinfunction "2_2") (pintype "passive"))
    )
    (net (code "25") (name "/M2.3") (class "Default")
      (node (ref "C15") (pin "1") (pinfunction "1_1") (pintype "passive"))
      (node (ref "IC2") (pin "6") (pinfunction "S3_6") (pintype "passive"))
      (node (ref "R79") (pin "2") (pinfunction "2_2") (pintype "passive"))
    )
    (net (code "26") (name "/M2.4") (class "Default")
      (node (ref "C7") (pin "1") (pinfunction "1_1") (pintype "passive"))
      (node (ref "IC2") (pin "7") (pinfunction "S4_7") (pintype "passive"))
      (node (ref "R39") (pin "2") (pinfunction "2_2") (pintype "passive"))
    )
    (net (code "27") (name "/M2.5") (class "Default")
      (node (ref "C5") (pin "1") (pinfunction "1_1") (pintype "passive"))
      (node (ref "IC2") (pin "12") (pinfunction "S5_12") (pintype "passive"))
      (node (ref "R37") (pin "2") (pinfunction "2_2") (pintype "passive"))
    )
    (net (code "28") (name "/M2.6") (class "Default")
      (node (ref "C13") (pin "1") (pinfunction "1_1") (pintype "passive"))
      (node (ref "IC2") (pin "11") (pinfunction "S6_11") (pintype "passive"))
      (node (ref "R77") (pin "2") (pinfunction "2_2") (pintype "passive"))
    )
    (net (code "29") (name "/M2.7") (class "Default")
      (node (ref "C6") (pin "1") (pinfunction "1_1") (pintype "passive"))
      (node (ref "IC2") (pin "10") (pinfunction "S7_10") (pintype "passive"))
      (node (ref "R38") (pin "2") (pinfunction "2_2") (pintype "passive"))
    )
    (net (code "30") (name "/M2.8") (class "Default")
      (node (ref "C14") (pin "1") (pinfunction "1_1") (pintype "passive"))
      (node (ref "IC2") (pin "9") (pinfunction "S8_9") (pintype "passive"))
      (node (ref "R78") (pin "2") (pinfunction "2_2") (pintype "passive"))
    )
    (net (code "31") (name "/NRST") (class "Default")
      (node (ref "C20") (pin "1") (pinfunction "1_1") (pintype "passive"))
      (node (ref "IC3") (pin "4") (pinfunction "NRST_4") (pintype "bidirectional"))
    )
    (net (code "32") (name "/P0.00{slash}XL1") (class "Default")
      (node (ref "C41") (pin "1") (pinfunction "1_1") (pintype "passive"))
      (node (ref "IC4") (pin "P$2") (pinfunction "P0.00/XL1_P$2") (pintype "bidirectional"))
      (node (ref "S1") (pin "1") (pinfunction "1_1") (pintype "passive"))
      (node (ref "S1") (pin "2") (pinfunction "2_2") (pintype "passive"))
      (node (ref "SW1") (pin "2") (pinfunction "S_2") (pintype "passive"))
    )
    (net (code "33") (name "/P0.01{slash}XL2") (class "Default")
      (node (ref "C42") (pin "1") (pinfunction "1_1") (pintype "passive"))
      (node (ref "IC4") (pin "P$3") (pinfunction "P0.01/XL2_P$3") (pintype "bidirectional"))
      (node (ref "S2") (pin "1") (pinfunction "1_1") (pintype "passive"))
      (node (ref "S2") (pin "2") (pinfunction "2_2") (pintype "passive"))
      (node (ref "SW2") (pin "2") (pinfunction "S_2") (pintype "passive"))
    )
    (net (code "34") (name "/P0.04") (class "Default")
      (node (ref "IC4") (pin "P$4") (pinfunction "P0.04/AIN2_P$4") (pintype "bidirectional"))
      (node (ref "R90") (pin "1") (pinfunction "1_1") (pintype "passive"))
    )
    (net (code "35") (name "/PA0") (class "Default")
      (node (ref "IC3") (pin "6") (pinfunction "PA0-CK_IN_6") (pintype "bidirectional"))
      (node (ref "R83") (pin "2") (pinfunction "2_2") (pintype "passive"))
    )
    (net (code "36") (name "/PA1") (class "Default")
      (node (ref "IC3") (pin "7") (pinfunction "PA1_7") (pintype "bidirectional"))
    )
    (net (code "37") (name "/PA2") (class "Default")
      (node (ref "C19") (pin "1") (pinfunction "1_1") (pintype "passive"))
      (node (ref "IC3") (pin "8") (pinfunction "PA2_8") (pintype "bidirectional"))
      (node (ref "R81") (pin "2") (pinfunction "2_2") (pintype "passive"))
      (node (ref "R82") (pin "1") (pinfunction "1_1") (pintype "passive"))
    )
    (net (code "38") (name "/PA3") (class "Default")
      (node (ref "IC3") (pin "9") (pinfunction "PA3_9") (pintype "bidirectional"))
      (node (ref "R101") (pin "2") (pinfunction "2_2") (pintype "passive"))
      (node (ref "U4") (pin "4") (pinfunction "SHDN#_4") (pintype "input"))
    )
    (net (code "39") (name "/PA10") (class "Default")
      (node (ref "IC3") (pin "20") (pinfunction "PA10_20") (pintype "bidirectional"))
      (node (ref "R85") (pin "1") (pinfunction "1_1") (pintype "passive"))
    )
    (net (code "40") (name "/PA15") (class "Default")
      (node (ref "IC3") (pin "23") (pinfunction "PA15_23") (pintype "bidirectional"))
      (node (ref "Q1") (pin "1") (pinfunction "G_1") (pintype "passive"))
      (node (ref "R103") (pin "1") (pinfunction "1_1") (pintype "passive"))
    )
    (net (code "41") (name "/PB0") (class "Default")
      (node (ref "IC3") (pin "14") (pinfunction "PB0_14") (pintype "bidirectional"))
      (node (ref "R89") (pin "1") (pinfunction "1_1") (pintype "passive"))
    )
    (net (code "42") (name "/PB1") (class "Default")
      (node (ref "IC3") (pin "15") (pinfunction "PB1_15") (pintype "bidirectional"))
      (node (ref "U1") (pin "6") (pinfunction "OUT_6") (pintype "output"))
    )
    (net (code "43") (name "/RF") (class "Default")
      (node (ref "L1") (pin "2") (pinfunction "2_2") (pintype "passive"))
      (node (ref "U$1") (pin "P$1") (pinfunction "P$1_P$1") (pintype "bidirectional"))
    )
    (net (code "44") (name "/S1") (class "Default")
      (node (ref "C1") (pin "2") (pinfunction "2_2") (pintype "passive"))
      (node (ref "R1") (pin "1") (pinfunction "1_1") (pintype "passive"))
      (node (ref "R17") (pin "1") (pinfunction "1_1") (pintype "passive"))
      (node (ref "R25") (pin "2") (pinfunction "2_2") (pintype "passive"))
      (node (ref "R9") (pin "1") (pinfunction "1_1") (pintype "passive"))
    )
    (net (code "45") (name "/S2") (class "Default")
      (node (ref "C2") (pin "2") (pinfunction "2_2") (pintype "passive"))
      (node (ref "R10") (pin "1") (pinfunction "1_1") (pintype "passive"))
      (node (ref "R18") (pin "1") (pinfunction "1_1") (pintype "passive"))
      (node (ref "R2") (pin "1") (pinfunction "1_1") (pintype "passive"))
      (node (ref "R26") (pin "2") (pinfunction "2_2") (pintype "passive"))
    )
    (net (code "46") (name "/S3") (class "Default")
      (node (ref "C3") (pin "2") (pinfunction "2_2") (pintype "passive"))
      (node (ref "R11") (pin "1") (pinfunction "1_1") (pintype "passive"))
      (node (ref "R19") (pin "1") (pinfunction "1_1") (pintype "passive"))
      (node (ref "R27") (pin "2") (pinfunction "2_2") (pintype "passive"))
      (node (ref "R3") (pin "1") (pinfunction "1_1") (pintype "passive"))
    )
    (net (code "47") (name "/S4") (class "Default")
      (node (ref "C4") (pin "2") (pinfunction "2_2") (pintype "passive"))
      (node (ref "R16") (pin "1") (pinfunction "1_1") (pintype "passive"))
      (node (ref "R20") (pin "1") (pinfunction "1_1") (pintype "passive"))
      (node (ref "R28") (pin "2") (pinfunction "2_2") (pintype "passive"))
      (node (ref "R8") (pin "1") (pinfunction "1_1") (pintype "passive"))
    )
    (net (code "48") (name "/S5") (class "Default")
      (node (ref "C5") (pin "2") (pinfunction "2_2") (pintype "passive"))
      (node (ref "R12") (pin "1") (pinfunction "1_1") (pintype "passive"))
      (node (ref "R21") (pin "1") (pinfunction "1_1") (pintype "passive"))
      (node (ref "R29") (pin "2") (pinfunction "2_2") (pintype "passive"))
      (node (ref "R4") (pin "1") (pinfunction "1_1") (pintype "passive"))
    )
    (net (code "49") (name "/S6") (class "Default")
      (node (ref "C6") (pin "2") (pinfunction "2_2") (pintype "passive"))
      (node (ref "R13") (pin "1") (pinfunction "1_1") (pintype "passive"))
      (node (ref "R22") (pin "1") (pinfunction "1_1") (pintype "passive"))
      (node (ref "R30") (pin "2") (pinfunction "2_2") (pintype "passive"))
      (node (ref "R5") (pin "1") (pinfunction "1_1") (pintype "passive"))
    )
    (net (code "50") (name "/S7") (class "Default")
      (node (ref "C7") (pin "2") (pinfunction "2_2") (pintype "passive"))
      (node (ref "R14") (pin "1") (pinfunction "1_1") (pintype "passive"))
      (node (ref "R23") (pin "1") (pinfunction "1_1") (pintype "passive"))
      (node (ref "R31") (pin "2") (pinfunction "2_2") (pintype "passive"))
      (node (ref "R6") (pin "1") (pinfunction "1_1") (pintype "passive"))
    )
    (net (code "51") (name "/S8") (class "Default")
      (node (ref "C8") (pin "2") (pinfunction "2_2") (pintype "passive"))
      (node (ref "R15") (pin "1") (pinfunction "1_1") (pintype "passive"))
      (node (ref "R24") (pin "1") (pinfunction "1_1") (pintype "passive"))
      (node (ref "R32") (pin "2") (pinfunction "2_2") (pintype "passive"))
      (node (ref "R7") (pin "1") (pinfunction "1_1") (pintype "passive"))
    )
    (net (code "52") (name "/S9") (class "Default")
      (node (ref "C9") (pin "2") (pinfunction "2_2") (pintype "passive"))
      (node (ref "R41") (pin "1") (pinfunction "1_1") (pintype "passive"))
      (node (ref "R49") (pin "1") (pinfunction "1_1") (pintype "passive"))
      (node (ref "R57") (pin "1") (pinfunction "1_1") (pintype "passive"))
      (node (ref "R65") (pin "2") (pinfunction "2_2") (pintype "passive"))
    )
    (net (code "53") (name "/S10") (class "Default")
      (node (ref "C10") (pin "2") (pinfunction "2_2") (pintype "passive"))
      (node (ref "R42") (pin "1") (pinfunction "1_1") (pintype "passive"))
      (node (ref "R50") (pin "1") (pinfunction "1_1") (pintype "passive"))
      (node (ref "R58") (pin "1") (pinfunction "1_1") (pintype "passive"))
      (node (ref "R66") (pin "2") (pinfunction "2_2") (pintype "passive"))
    )
    (net (code "54") (name "/S11") (class "Default")
      (node (ref "C11") (pin "2") (pinfunction "2_2") (pintype "passive"))
      (node (ref "R43") (pin "1") (pinfunction "1_1") (pintype "passive"))
      (node (ref "R51") (pin "1") (pinfunction "1_1") (pintype "passive"))
      (node (ref "R59") (pin "1") (pinfunction "1_1") (pintype "passive"))
      (node (ref "R67") (pin "2") (pinfunction "2_2") (pintype "passive"))
    )
    (net (code "55") (name "/S12") (class "Default")
      (node (ref "C12") (pin "2") (pinfunction "2_2") (pintype "passive"))
      (node (ref "R44") (pin "1") (pinfunction "1_1") (pintype "passive"))
      (node (ref "R52") (pin "1") (pinfunction "1_1") (pintype "passive"))
      (node (ref "R60") (pin "1") (pinfunction "1_1") (pintype "passive"))
      (node (ref "R68") (pin "2") (pinfunction "2_2") (pintype "passive"))
    )
    (net (code "56") (name "/S13") (class "Default")
      (node (ref "C13") (pin "2") (pinfunction "2_2") (pintype "passive"))
      (node (ref "R45") (pin "1") (pinfunction "1_1") (pintype "passive"))
      (node (ref "R53") (pin "1") (pinfunction "1_1") (pintype "passive"))
      (node (ref "R61") (pin "1") (pinfunction "1_1") (pintype "passive"))
      (node (ref "R69") (pin "2") (pinfunction "2_2") (pintype "passive"))
    )
    (net (code "57") (name "/S14") (class "Default")
      (node (ref "C14") (pin "2") (pinfunction "2_2") (pintype "passive"))
      (node (ref "R46") (pin "1") (pinfunction "1_1") (pintype "passive"))
      (node (ref "R54") (pin "1") (pinfunction "1_1") (pintype "passive"))
      (node (ref "R62") (pin "1") (pinfunction "1_1") (pintype "passive"))
      (node (ref "R70") (pin "2") (pinfunction "2_2") (pintype "passive"))
    )
    (net (code "58") (name "/S15") (class "Default")
      (node (ref "C15") (pin "2") (pinfunction "2_2") (pintype "passive"))
      (node (ref "R47") (pin "1") (pinfunction "1_1") (pintype "passive"))
      (node (ref "R55") (pin "1") (pinfunction "1_1") (pintype "passive"))
      (node (ref "R63") (pin "1") (pinfunction "1_1") (pintype "passive"))
      (node (ref "R71") (pin "2") (pinfunction "2_2") (pintype "passive"))
    )
    (net (code "59") (name "/S16") (class "Default")
      (node (ref "C16") (pin "2") (pinfunction "2_2") (pintype "passive"))
      (node (ref "R48") (pin "1") (pinfunction "1_1") (pintype "passive"))
      (node (ref "R56") (pin "1") (pinfunction "1_1") (pintype "passive"))
      (node (ref "R64") (pin "1") (pinfunction "1_1") (pintype "passive"))
      (node (ref "R72") (pin "2") (pinfunction "2_2") (pintype "passive"))
    )
    (net (code "60") (name "/S21") (class "Default")
      (node (ref "R1") (pin "2") (pinfunction "2_2") (pintype "passive"))
    )
    (net (code "61") (name "/S22") (class "Default")
      (node (ref "R2") (pin "2") (pinfunction "2_2") (pintype "passive"))
    )
    (net (code "62") (name "/S23") (class "Default")
      (node (ref "R3") (pin "2") (pinfunction "2_2") (pintype "passive"))
    )
    (net (code "63") (name "/S24") (class "Default")
      (node (ref "R8") (pin "2") (pinfunction "2_2") (pintype "passive"))
    )
    (net (code "64") (name "/S25") (class "Default")
      (node (ref "R4") (pin "2") (pinfunction "2_2") (pintype "passive"))
    )
    (net (code "65") (name "/S26") (class "Default")
      (node (ref "R5") (pin "2") (pinfunction "2_2") (pintype "passive"))
    )
    (net (code "66") (name "/S27") (class "Default")
      (node (ref "R6") (pin "2") (pinfunction "2_2") (pintype "passive"))
    )
    (net (code "67") (name "/S28") (class "Default")
      (node (ref "R7") (pin "2") (pinfunction "2_2") (pintype "passive"))
    )
    (net (code "68") (name "/S29") (class "Default")
      (node (ref "R41") (pin "2") (pinfunction "2_2") (pintype "passive"))
    )
    (net (code "69") (name "/S31") (class "Default")
      (node (ref "R9") (pin "2") (pinfunction "2_2") (pintype "passive"))
    )
    (net (code "70") (name "/S32") (class "Default")
      (node (ref "R10") (pin "2") (pinfunction "2_2") (pintype "passive"))
    )
    (net (code "71") (name "/S33") (class "Default")
      (node (ref "R11") (pin "2") (pinfunction "2_2") (pintype "passive"))
    )
    (net (code "72") (name "/S34") (class "Default")
      (node (ref "R16") (pin "2") (pinfunction "2_2") (pintype "passive"))
    )
    (net (code "73") (name "/S35") (class "Default")
      (node (ref "R12") (pin "2") (pinfunction "2_2") (pintype "passive"))
    )
    (net (code "74") (name "/S36") (class "Default")
      (node (ref "R13") (pin "2") (pinfunction "2_2") (pintype "passive"))
    )
    (net (code "75") (name "/S37") (class "Default")
      (node (ref "R14") (pin "2") (pinfunction "2_2") (pintype "passive"))
    )
    (net (code "76") (name "/S38") (class "Default")
      (node (ref "R15") (pin "2") (pinfunction "2_2") (pintype "passive"))
    )
    (net (code "77") (name "/S39") (class "Default")
      (node (ref "R49") (pin "2") (pinfunction "2_2") (pintype "passive"))
    )
    (net (code "78") (name "/S41") (class "Default")
      (node (ref "R17") (pin "2") (pinfunction "2_2") (pintype "passive"))
    )
    (net (code "79") (name "/S42") (class "Default")
      (node (ref "R18") (pin "2") (pinfunction "2_2") (pintype "passive"))
    )
    (net (code "80") (name "/S43") (class "Default")
      (node (ref "R19") (pin "2") (pinfunction "2_2") (pintype "passive"))
    )
    (net (code "81") (name "/S44") (class "Default")
      (node (ref "R20") (pin "2") (pinfunction "2_2") (pintype "passive"))
    )
    (net (code "82") (name "/S45") (class "Default")
      (node (ref "R21") (pin "2") (pinfunction "2_2") (pintype "passive"))
    )
    (net (code "83") (name "/S46") (class "Default")
      (node (ref "R22") (pin "2") (pinfunction "2_2") (pintype "passive"))
    )
    (net (code "84") (name "/S47") (class "Default")
      (node (ref "R23") (pin "2") (pinfunction "2_2") (pintype "passive"))
    )
    (net (code "85") (name "/S48") (class "Default")
      (node (ref "R24") (pin "2") (pinfunction "2_2") (pintype "passive"))
    )
    (net (code "86") (name "/S49") (class "Default")
      (node (ref "R57") (pin "2") (pinfunction "2_2") (pintype "passive"))
    )
    (net (code "87") (name "/S210") (class "Default")
      (node (ref "R42") (pin "2") (pinfunction "2_2") (pintype "passive"))
    )
    (net (code "88") (name "/S211") (class "Default")
      (node (ref "R43") (pin "2") (pinfunction "2_2") (pintype "passive"))
    )
    (net (code "89") (name "/S212") (class "Default")
      (node (ref "R44") (pin "2") (pinfunction "2_2") (pintype "passive"))
    )
    (net (code "90") (name "/S213") (class "Default")
      (node (ref "R45") (pin "2") (pinfunction "2_2") (pintype "passive"))
    )
    (net (code "91") (name "/S214") (class "Default")
      (node (ref "R46") (pin "2") (pinfunction "2_2") (pintype "passive"))
    )
    (net (code "92") (name "/S215") (class "Default")
      (node (ref "R47") (pin "2") (pinfunction "2_2") (pintype "passive"))
    )
    (net (code "93") (name "/S216") (class "Default")
      (node (ref "R48") (pin "2") (pinfunction "2_2") (pintype "passive"))
    )
    (net (code "94") (name "/S310") (class "Default")
      (node (ref "R50") (pin "2") (pinfunction "2_2") (pintype "passive"))
    )
    (net (code "95") (name "/S311") (class "Default")
      (node (ref "R51") (pin "2") (pinfunction "2_2") (pintype "passive"))
    )
    (net (code "96") (name "/S312") (class "Default")
      (node (ref "R52") (pin "2") (pinfunction "2_2") (pintype "passive"))
    )
    (net (code "97") (name "/S313") (class "Default")
      (node (ref "R53") (pin "2") (pinfunction "2_2") (pintype "passive"))
    )
    (net (code "98") (name "/S314") (class "Default")
      (node (ref "R54") (pin "2") (pinfunction "2_2") (pintype "passive"))
    )
    (net (code "99") (name "/S315") (class "Default")
      (node (ref "R55") (pin "2") (pinfunction "2_2") (pintype "passive"))
    )
    (net (code "100") (name "/S316") (class "Default")
      (node (ref "R56") (pin "2") (pinfunction "2_2") (pintype "passive"))
    )
    (net (code "101") (name "/S410") (class "Default")
      (node (ref "R58") (pin "2") (pinfunction "2_2") (pintype "passive"))
    )
    (net (code "102") (name "/S411") (class "Default")
      (node (ref "R59") (pin "2") (pinfunction "2_2") (pintype "passive"))
    )
    (net (code "103") (name "/S412") (class "Default")
      (node (ref "R60") (pin "2") (pinfunction "2_2") (pintype "passive"))
    )
    (net (code "104") (name "/S413") (class "Default")
      (node (ref "R61") (pin "2") (pinfunction "2_2") (pintype "passive"))
    )
    (net (code "105") (name "/S414") (class "Default")
      (node (ref "R62") (pin "2") (pinfunction "2_2") (pintype "passive"))
    )
    (net (code "106") (name "/S415") (class "Default")
      (node (ref "R63") (pin "2") (pinfunction "2_2") (pintype "passive"))
    )
    (net (code "107") (name "/S416") (class "Default")
      (node (ref "R64") (pin "2") (pinfunction "2_2") (pintype "passive"))
    )
    (net (code "108") (name "/ST_SWCLK") (class "Default")
      (node (ref "IC3") (pin "22") (pinfunction "PA14_22") (pintype "bidirectional"))
    )
    (net (code "109") (name "/ST_SWDIO") (class "Default")
      (node (ref "IC3") (pin "21") (pinfunction "PA13_21") (pintype "bidirectional"))
    )
    (net (code "110") (name "GND") (class "Default")
      (node (ref "C17") (pin "2") (pinfunction "2_2") (pintype "passive"))
      (node (ref "C18") (pin "2") (pinfunction "2_2") (pintype "passive"))
      (node (ref "C19") (pin "2") (pinfunction "2_2") (pintype "passive"))
      (node (ref "C20") (pin "2") (pinfunction "2_2") (pintype "passive"))
      (node (ref "C21") (pin "2") (pinfunction "2_2") (pintype "passive"))
      (node (ref "C22") (pin "2") (pinfunction "2_2") (pintype "passive"))
      (node (ref "C23") (pin "2") (pinfunction "2_2") (pintype "passive"))
      (node (ref "C24") (pin "2") (pinfunction "2_2") (pintype "passive"))
      (node (ref "C25") (pin "2") (pinfunction "2_2") (pintype "passive"))
      (node (ref "C26") (pin "2") (pinfunction "2_2") (pintype "passive"))
      (node (ref "C27") (pin "2") (pinfunction "2_2") (pintype "passive"))
      (node (ref "C28") (pin "2") (pinfunction "2_2") (pintype "passive"))
      (node (ref "C29") (pin "2") (pinfunction "2_2") (pintype "passive"))
      (node (ref "C30") (pin "2") (pinfunction "2_2") (pintype "passive"))
      (node (ref "C31") (pin "2") (pinfunction "2_2") (pintype "passive"))
      (node (ref "C33") (pin "2") (pinfunction "2_2") (pintype "passive"))
      (node (ref "C34") (pin "2") (pinfunction "2_2") (pintype "passive"))
      (node (ref "C35") (pin "2") (pinfunction "2_2") (pintype "passive"))
      (node (ref "C36") (pin "2") (pinfunction "2_2") (pintype "passive"))
      (node (ref "C37") (pin "2") (pinfunction "2_2") (pintype "passive"))
      (node (ref "C38") (pin "1") (pinfunction "1_1") (pintype "passive"))
      (node (ref "C40") (pin "1") (pinfunction "1_1") (pintype "passive"))
      (node (ref "C41") (pin "2") (pinfunction "2_2") (pintype "passive"))
      (node (ref "C42") (pin "2") (pinfunction "2_2") (pintype "passive"))
      (node (ref "C43") (pin "2") (pinfunction "2_2") (pintype "passive"))
      (node (ref "IC1") (pin "14") (pinfunction "GND_14") (pintype "power_in"))
      (node (ref "IC1") (pin "3") (pinfunction "V-_3") (pintype "power_in"))
      (node (ref "IC2") (pin "14") (pinfunction "GND_14") (pintype "power_in"))
      (node (ref "IC2") (pin "3") (pinfunction "V-_3") (pintype "power_in"))
      (node (ref "IC3") (pin "16") (pinfunction "VSS_16") (pintype "power_in"))
      (node (ref "IC3") (pin "27") (pinfunction "BOOT0_27") (pintype "input"))
      (node (ref "IC3") (pin "28") (pinfunction "VSS_28") (pintype "power_in"))
      (node (ref "IC4") (pin "P$20") (pinfunction "VSS_P$20") (pintype "bidirectional"))
      (node (ref "IC4") (pin "P$29") (pinfunction "VSS_P$29") (pintype "bidirectional"))
      (node (ref "IC4") (pin "P$33") (pinfunction "VSS_P$33") (pintype "bidirectional"))
      (node (ref "IC4") (pin "P$34") (pinfunction "VSS_P$34") (pintype "bidirectional"))
      (node (ref "IC4") (pin "P$35") (pinfunction "VSS_P$35") (pintype "bidirectional"))
      (node (ref "IC4") (pin "P$36") (pinfunction "VSS_P$36") (pintype "bidirectional"))
      (node (ref "IC4") (pin "P$37") (pinfunction "VSS_P$37") (pintype "bidirectional"))
      (node (ref "IC4") (pin "P$38") (pinfunction "VSS_P$38") (pintype "bidirectional"))
      (node (ref "IC4") (pin "P$39") (pinfunction "VSS_P$39") (pintype "bidirectional"))
      (node (ref "IC4") (pin "P$40") (pinfunction "VSS_P$40") (pintype "bidirectional"))
      (node (ref "IC4") (pin "P$41") (pinfunction "VSS_P$41") (pintype "bidirectional"))
      (node (ref "IC4") (pin "P$42") (pinfunction "VSS_P$42") (pintype "bidirectional"))
      (node (ref "LED1-G") (pin "C") (pinfunction "C_C") (pintype "passive"))
      (node (ref "LED4-G") (pin "C") (pinfunction "C_C") (pintype "passive"))
      (node (ref "LED5-R") (pin "C") (pinfunction "C_C") (pintype "passive"))
      (node (ref "Q1") (pin "2") (pinfunction "S_2") (pintype "passive"))
      (node (ref "R100") (pin "2") (pinfunction "2_2") (pintype "passive"))
      (node (ref "R102") (pin "2") (pinfunction "2_2") (pintype "passive"))
      (node (ref "R103") (pin "2") (pinfunction "2_2") (pintype "passive"))
      (node (ref "R25") (pin "1") (pinfunction "1_1") (pintype "passive"))
      (node (ref "R26") (pin "1") (pinfunction "1_1") (pintype "passive"))
      (node (ref "R27") (pin "1") (pinfunction "1_1") (pintype "passive"))
      (node (ref "R28") (pin "1") (pinfunction "1_1") (pintype "passive"))
      (node (ref "R29") (pin "1") (pinfunction "1_1") (pintype "passive"))
      (node (ref "R30") (pin "1") (pinfunction "1_1") (pintype "passive"))
      (node (ref "R31") (pin "1") (pinfunction "1_1") (pintype "passive"))
      (node (ref "R32") (pin "1") (pinfunction "1_1") (pintype "passive"))
      (node (ref "R33") (pin "1") (pinfunction "1_1") (pintype "passive"))
      (node (ref "R34") (pin "1") (pinfunction "1_1") (pintype "passive"))
      (node (ref "R35") (pin "1") (pinfunction "1_1") (pintype "passive"))
      (node (ref "R36") (pin "1") (pinfunction "1_1") (pintype "passive"))
      (node (ref "R37") (pin "1") (pinfunction "1_1") (pintype "passive"))
      (node (ref "R38") (pin "1") (pinfunction "1_1") (pintype "passive"))
      (node (ref "R39") (pin "1") (pinfunction "1_1") (pintype "passive"))
      (node (ref "R40") (pin "1") (pinfunction "1_1") (pintype "passive"))
      (node (ref "R65") (pin "1") (pinfunction "1_1") (pintype "passive"))
      (node (ref "R66") (pin "1") (pinfunction "1_1") (pintype "passive"))
      (node (ref "R67") (pin "1") (pinfunction "1_1") (pintype "passive"))
      (node (ref "R68") (pin "1") (pinfunction "1_1") (pintype "passive"))
      (node (ref "R69") (pin "1") (pinfunction "1_1") (pintype "passive"))
      (node (ref "R70") (pin "1") (pinfunction "1_1") (pintype "passive"))
      (node (ref "R71") (pin "1") (pinfunction "1_1") (pintype "passive"))
      (node (ref "R72") (pin "1") (pinfunction "1_1") (pintype "passive"))
      (node (ref "R73") (pin "1") (pinfunction "1_1") (pintype "passive"))
      (node (ref "R74") (pin "1") (pinfunction "1_1") (pintype "passive"))
      (node (ref "R75") (pin "1") (pinfunction "1_1") (pintype "passive"))
      (node (ref "R76") (pin "1") (pinfunction "1_1") (pintype "passive"))
      (node (ref "R77") (pin "1") (pinfunction "1_1") (pintype "passive"))
      (node (ref "R78") (pin "1") (pinfunction "1_1") (pintype "passive"))
      (node (ref "R79") (pin "1") (pinfunction "1_1") (pintype "passive"))
      (node (ref "R80") (pin "1") (pinfunction "1_1") (pintype "passive"))
      (node (ref "R82") (pin "2") (pinfunction "2_2") (pintype "passive"))
      (node (ref "R99") (pin "2") (pinfunction "2_2") (pintype "passive"))
      (node (ref "S1") (pin "3") (pinfunction "3_3") (pintype "passive"))
      (node (ref "S1") (pin "4") (pinfunction "4_4") (pintype "passive"))
      (node (ref "S2") (pin "3") (pinfunction "3_3") (pintype "passive"))
      (node (ref "S2") (pin "4") (pinfunction "4_4") (pintype "passive"))
      (node (ref "SW1") (pin "1") (pinfunction "P_1") (pintype "passive"))
      (node (ref "SW2") (pin "1") (pinfunction "P_1") (pintype "passive"))
      (node (ref "U1") (pin "1") (pinfunction "REF_1") (pintype "input"))
      (node (ref "U1") (pin "2") (pinfunction "GND_2") (pintype "passive"))
      (node (ref "U2") (pin "2") (pinfunction "GND_2") (pintype "passive"))
      (node (ref "U3") (pin "2") (pinfunction "VSS_2") (pintype "bidirectional"))
      (node (ref "U4") (pin "2") (pinfunction "GND_2") (pintype "power_in"))
      (node (ref "U5") (pin "5") (pinfunction "5_5") (pintype "input"))
      (node (ref "X1") (pin "2") (pinfunction "2_2") (pintype "passive"))
      (node (ref "X1") (pin "4") (pinfunction "4_4") (pintype "passive"))
    )
    (net (code "111") (name "Net-(C33-Pad1)") (class "Default")
      (node (ref "C33") (pin "1") (pinfunction "1_1") (pintype "passive"))
      (node (ref "R89") (pin "2") (pinfunction "2_2") (pintype "passive"))
      (node (ref "R90") (pin "2") (pinfunction "2_2") (pintype "passive"))
      (node (ref "R96") (pin "2") (pinfunction "2_2") (pintype "passive"))
      (node (ref "R99") (pin "1") (pinfunction "1_1") (pintype "passive"))
    )
    (net (code "112") (name "Net-(IC4-ANT)") (class "Default")
      (node (ref "C23") (pin "1") (pinfunction "1_1") (pintype "passive"))
      (node (ref "IC4") (pin "P$19") (pinfunction "ANT_P$19") (pintype "bidirectional"))
      (node (ref "L1") (pin "1") (pinfunction "1_1") (pintype "passive"))
    )
    (net (code "113") (name "Net-(IC4-P0.12)") (class "Default")
      (node (ref "IC4") (pin "P$10") (pinfunction "P0.12_P$10") (pintype "bidirectional"))
      (node (ref "R84") (pin "2") (pinfunction "2_2") (pintype "passive"))
    )
    (net (code "114") (name "Net-(IC4-XC1)") (class "Default")
      (node (ref "C30") (pin "1") (pinfunction "1_1") (pintype "passive"))
      (node (ref "IC4") (pin "P$23") (pinfunction "XC1_P$23") (pintype "bidirectional"))
      (node (ref "X1") (pin "1") (pinfunction "1_1") (pintype "passive"))
    )
    (net (code "115") (name "Net-(IC4-XC2)") (class "Default")
      (node (ref "C29") (pin "1") (pinfunction "1_1") (pintype "passive"))
      (node (ref "IC4") (pin "P$24") (pinfunction "XC2_P$24") (pintype "bidirectional"))
      (node (ref "X1") (pin "3") (pinfunction "3_3") (pintype "passive"))
    )
    (net (code "116") (name "Net-(LED1-G-PadA)") (class "Default")
      (node (ref "LED1-G") (pin "A") (pinfunction "A_A") (pintype "passive"))
      (node (ref "R97") (pin "1") (pinfunction "1_1") (pintype "passive"))
    )
    (net (code "117") (name "Net-(LED2-R-PadC)") (class "Default")
      (node (ref "LED2-R") (pin "C") (pinfunction "C_C") (pintype "passive"))
      (node (ref "R98") (pin "1") (pinfunction "1_1") (pintype "passive"))
    )
    (net (code "118") (name "Net-(LED3-BLU)") (class "Default")
      (node (ref "LED3") (pin "B") (pinfunction "BLU_B") (pintype "bidirectional"))
      (node (ref "R94") (pin "1") (pinfunction "1_1") (pintype "passive"))
    )
    (net (code "119") (name "Net-(LED3-GRN)") (class "Default")
      (node (ref "LED3") (pin "G") (pinfunction "GRN_G") (pintype "bidirectional"))
      (node (ref "R92") (pin "1") (pinfunction "1_1") (pintype "passive"))
    )
    (net (code "120") (name "Net-(LED3-RED)") (class "Default")
      (node (ref "LED3") (pin "R") (pinfunction "RED_R") (pintype "bidirectional"))
      (node (ref "R93") (pin "1") (pinfunction "1_1") (pintype "passive"))
    )
    (net (code "121") (name "Net-(LED4-G-PadA)") (class "Default")
      (node (ref "LED4-G") (pin "A") (pinfunction "A_A") (pintype "passive"))
      (node (ref "R83") (pin "1") (pinfunction "1_1") (pintype "passive"))
    )
    (net (code "122") (name "Net-(LED5-R-PadA)") (class "Default")
      (node (ref "LED5-R") (pin "A") (pinfunction "A_A") (pintype "passive"))
      (node (ref "R84") (pin "1") (pinfunction "1_1") (pintype "passive"))
    )
    (net (code "123") (name "Net-(Q1-D)") (class "Default")
      (node (ref "Q1") (pin "3") (pinfunction "D_3") (pintype "passive"))
      (node (ref "R104") (pin "2") (pinfunction "2_2") (pintype "passive"))
    )
    (net (code "124") (name "Net-(U1-IN+)") (class "Default")
      (node (ref "C32") (pin "1") (pinfunction "1_1") (pintype "passive"))
      (node (ref "R91") (pin "1") (pinfunction "1_1") (pintype "passive"))
      (node (ref "U1") (pin "4") (pinfunction "IN+_4") (pintype "input"))
    )
    (net (code "125") (name "Net-(U1-IN-)") (class "Default")
      (node (ref "C32") (pin "2") (pinfunction "2_2") (pintype "passive"))
      (node (ref "R87") (pin "1") (pinfunction "1_1") (pintype "passive"))
      (node (ref "U1") (pin "5") (pinfunction "IN-_5") (pintype "input"))
    )
    (net (code "126") (name "Net-(U1-V+)") (class "Default")
      (node (ref "C40") (pin "2") (pinfunction "2_2") (pintype "passive"))
      (node (ref "R85") (pin "2") (pinfunction "2_2") (pintype "passive"))
      (node (ref "R86") (pin "2") (pinfunction "2_2") (pintype "passive"))
      (node (ref "U1") (pin "3") (pinfunction "V+_3") (pintype "power_in"))
    )
    (net (code "127") (name "Net-(U3-PROG)") (class "Default")
      (node (ref "R100") (pin "1") (pinfunction "1_1") (pintype "passive"))
      (node (ref "U3") (pin "5") (pinfunction "PROG_5") (pintype "bidirectional"))
    )
    (net (code "128") (name "Net-(U3-STAT)") (class "Default")
      (node (ref "R97") (pin "2") (pinfunction "2_2") (pintype "passive"))
      (node (ref "R98") (pin "2") (pinfunction "2_2") (pintype "passive"))
      (node (ref "U3") (pin "1") (pinfunction "STAT_1") (pintype "bidirectional"))
    )
    (net (code "129") (name "Net-(U4-FB)") (class "Default")
      (node (ref "C39") (pin "2") (pinfunction "2_2") (pintype "passive"))
      (node (ref "R102") (pin "1") (pinfunction "1_1") (pintype "passive"))
      (node (ref "R104") (pin "1") (pinfunction "1_1") (pintype "passive"))
      (node (ref "R95") (pin "2") (pinfunction "2_2") (pintype "passive"))
      (node (ref "U4") (pin "3") (pinfunction "FB_3") (pintype "input"))
    )
    (net (code "130") (name "Net-(U4-SW)") (class "Default")
      (node (ref "D1") (pin "A") (pinfunction "A_A") (pintype "passive"))
      (node (ref "L2") (pin "2") (pinfunction "2_2") (pintype "passive"))
      (node (ref "U4") (pin "1") (pinfunction "SW_1") (pintype "passive"))
    )
    (net (code "131") (name "P0.18{slash}SWO") (class "Default")
      (node (ref "IC4") (pin "P$14") (pinfunction "P0.18_P$14") (pintype "bidirectional"))
    )
    (net (code "132") (name "P0.20") (class "Default")
      (node (ref "IC4") (pin "P$15") (pinfunction "P0.20_P$15") (pintype "bidirectional"))
    )
    (net (code "133") (name "P0.21{slash}RESET") (class "Default")
      (node (ref "IC4") (pin "P$16") (pinfunction "P0.21/RESET_P$16") (pintype "bidirectional"))
    )
    (net (code "134") (name "P0.25") (class "Default")
      (node (ref "IC4") (pin "P$26") (pinfunction "P0.25_P$26") (pintype "bidirectional"))
      (node (ref "R92") (pin "2") (pinfunction "2_2") (pintype "passive"))
    )
    (net (code "135") (name "P0.28") (class "Default")
      (node (ref "IC4") (pin "P$27") (pinfunction "P0.28/AIN4_P$27") (pintype "bidirectional"))
      (node (ref "R93") (pin "2") (pinfunction "2_2") (pintype "passive"))
    )
    (net (code "136") (name "P0.30") (class "Default")
      (node (ref "IC4") (pin "P$28") (pinfunction "P0.30/AIN6_P$28") (pintype "bidirectional"))
      (node (ref "R94") (pin "2") (pinfunction "2_2") (pintype "passive"))
    )
    (net (code "137") (name "SPI1_MISO") (class "Default")
      (node (ref "IC3") (pin "12") (pinfunction "PA6_12") (pintype "bidirectional"))
      (node (ref "IC4") (pin "P$6") (pinfunction "P0.06_P$6") (pintype "bidirectional"))
    )
    (net (code "138") (name "SPI1_MOSI") (class "Default")
      (node (ref "IC3") (pin "13") (pinfunction "PA7_13") (pintype "bidirectional"))
      (node (ref "IC4") (pin "P$5") (pinfunction "P0.05/AIN3_P$5") (pintype "bidirectional"))
    )
    (net (code "139") (name "SPI1_NSS") (class "Default")
      (node (ref "IC3") (pin "10") (pinfunction "PA4_10") (pintype "bidirectional"))
      (node (ref "IC4") (pin "P$8") (pinfunction "P0.10_P$8") (pintype "bidirectional"))
    )
    (net (code "140") (name "SPI1_SCK") (class "Default")
      (node (ref "IC3") (pin "11") (pinfunction "PA5_11") (pintype "bidirectional"))
      (node (ref "IC4") (pin "P$7") (pinfunction "P0.09_P$7") (pintype "bidirectional"))
    )
    (net (code "141") (name "SPI_ANSWER") (class "Default")
      (node (ref "IC3") (pin "18") (pinfunction "PA8_18") (pintype "bidirectional"))
      (node (ref "IC4") (pin "P$13") (pinfunction "P0.16_P$13") (pintype "bidirectional"))
    )
    (net (code "142") (name "STM32_SLEEP") (class "Default")
      (node (ref "IC3") (pin "19") (pinfunction "PA9_19") (pintype "bidirectional"))
      (node (ref "IC4") (pin "P$12") (pinfunction "P0.15_P$12") (pintype "bidirectional"))
    )
    (net (code "143") (name "SWDCLK") (class "Default")
      (node (ref "IC4") (pin "P$17") (pinfunction "SWDCLK_P$17") (pintype "bidirectional"))
    )
    (net (code "144") (name "SWDIO") (class "Default")
      (node (ref "IC4") (pin "P$18") (pinfunction "SWDIO_P$18") (pintype "bidirectional"))
    )
    (net (code "145") (name "unconnected-(IC4-DCC-PadP$31)") (class "Default")
      (node (ref "IC4") (pin "P$31") (pinfunction "DCC_P$31") (pintype "bidirectional"))
    )
    (net (code "146") (name "unconnected-(IC4-P0.14-PadP$11)") (class "Default")
      (node (ref "IC4") (pin "P$11") (pinfunction "P0.14_P$11") (pintype "bidirectional"))
    )
    (net (code "147") (name "unconnected-(U2-NC-Pad4)") (class "Default")
      (node (ref "U2") (pin "4") (pinfunction "NC_4") (pintype "no_connect"))
    )
    (net (code "148") (name "unconnected-(U5-GND1-PadCASING1)") (class "Default")
      (node (ref "U5") (pin "CASING1") (pinfunction "GND1_CASING1") (pintype "bidirectional"))
    )
    (net (code "149") (name "unconnected-(U5-GND2-PadCASING2)") (class "Default")
      (node (ref "U5") (pin "CASING2") (pinfunction "GND2_CASING2") (pintype "bidirectional"))
    )
    (net (code "150") (name "unconnected-(U5-GND3-PadCASING3)") (class "Default")
      (node (ref "U5") (pin "CASING3") (pinfunction "GND3_CASING3") (pintype "bidirectional"))
    )
    (net (code "151") (name "unconnected-(U5-GND4-PadCASING4)") (class "Default")
      (node (ref "U5") (pin "CASING4") (pinfunction "GND4_CASING4") (pintype "bidirectional"))
    )
    (net (code "152") (name "unconnected-(U5-Pad2)") (class "Default")
      (node (ref "U5") (pin "2") (pinfunction "2_2") (pintype "input"))
    )
    (net (code "153") (name "unconnected-(U5-Pad3)") (class "Default")
      (node (ref "U5") (pin "3") (pinfunction "3_3") (pintype "input"))
    )
    (net (code "154") (name "unconnected-(U5-Pad4)") (class "Default")
      (node (ref "U5") (pin "4") (pinfunction "4_4") (pintype "input"))
    )
    (net (code "155") (name "unconnected-(С1-Pad1)") (class "Default")
      (node (ref "С1") (pin "1") (pinfunction "1_1") (pintype "passive"))
    )
    (net (code "156") (name "unconnected-(С1-Pad2)") (class "Default")
      (node (ref "С1") (pin "2") (pinfunction "2_2") (pintype "passive"))
    )
    (net (code "157") (name "unconnected-(С2-Pad1)") (class "Default")
      (node (ref "С2") (pin "1") (pinfunction "1_1") (pintype "passive"))
    )
    (net (code "158") (name "unconnected-(С2-Pad2)") (class "Default")
      (node (ref "С2") (pin "2") (pinfunction "2_2") (pintype "passive"))
    )
    (net (code "159") (name "unconnected-(С3-Pad1)") (class "Default")
      (node (ref "С3") (pin "1") (pinfunction "1_1") (pintype "passive"))
    )
    (net (code "160") (name "unconnected-(С3-Pad2)") (class "Default")
      (node (ref "С3") (pin "2") (pinfunction "2_2") (pintype "passive"))
    )
    (net (code "161") (name "unconnected-(С4-Pad1)") (class "Default")
      (node (ref "С4") (pin "1") (pinfunction "1_1") (pintype "passive"))
    )
    (net (code "162") (name "unconnected-(С4-Pad2)") (class "Default")
      (node (ref "С4") (pin "2") (pinfunction "2_2") (pintype "passive"))
    )
  )
)
